# untitled.net
KiCad netlist of a schematic drawn in EAGLE
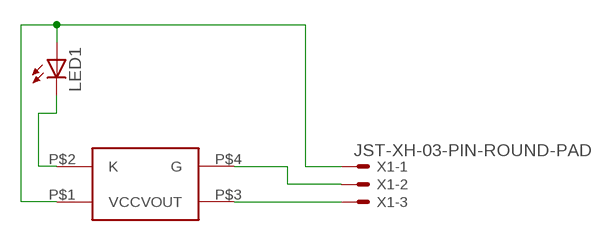
[diagram p0: schematic, sheet 1]

(export (version "E")
  (design (tool "Eeschema 10.0.6"))
  (components
    (comp (ref "LED1")
      (value "LED3MM")
      (footprint "eagle-import:LED3MM")
      (libsource (lib "eagle-import") (part "LED3MM"))
    )
    (comp (ref "U$1")
      (value "S4282-51")
      (footprint "eagle-import:S4282-51")
      (libsource (lib "eagle-import") (part "S4282-51"))
    )
    (comp (ref "X1")
      (value "JST-XH-03-PIN-ROUND-PAD")
      (footprint "eagle-import:JST-XH-03-PACKAGE-ROUND-PAD")
      (libsource (lib "eagle-import") (part "JST-XH-03-PIN-ROUND-PAD"))
    )
  )
  (nets
    (net (code "1") (name "Net-(LED1-C)") (class "Default")
      (node (ref "LED1") (pin "K") (pinfunction "C_K") (pintype "passive"))
      (node (ref "U$1") (pin "P$2") (pinfunction "K_P$2") (pintype "bidirectional"))
    )
    (net (code "2") (name "Net-(U$1-G)") (class "Default")
      (node (ref "U$1") (pin "P$4") (pinfunction "G_P$4") (pintype "bidirectional"))
      (node (ref "X1") (pin "2") (pinfunction "S_2") (pintype "passive"))
    )
    (net (code "3") (name "Net-(U$1-VCC)") (class "Default")
      (node (ref "LED1") (pin "A") (pinfunction "A_A") (pintype "passive"))
      (node (ref "U$1") (pin "P$1") (pinfunction "VCC_P$1") (pintype "bidirectional"))
      (node (ref "X1") (pin "1") (pinfunction "S_1") (pintype "passive"))
    )
    (net (code "4") (name "Net-(U$1-VOUT)") (class "Default")
      (node (ref "U$1") (pin "P$3") (pinfunction "VOUT_P$3") (pintype "bidirectional"))
      (node (ref "X1") (pin "3") (pinfunction "S_3") (pintype "passive"))
    )
  )
)
